# keyboard.net
KiCad netlist of a schematic drawn in EAGLE
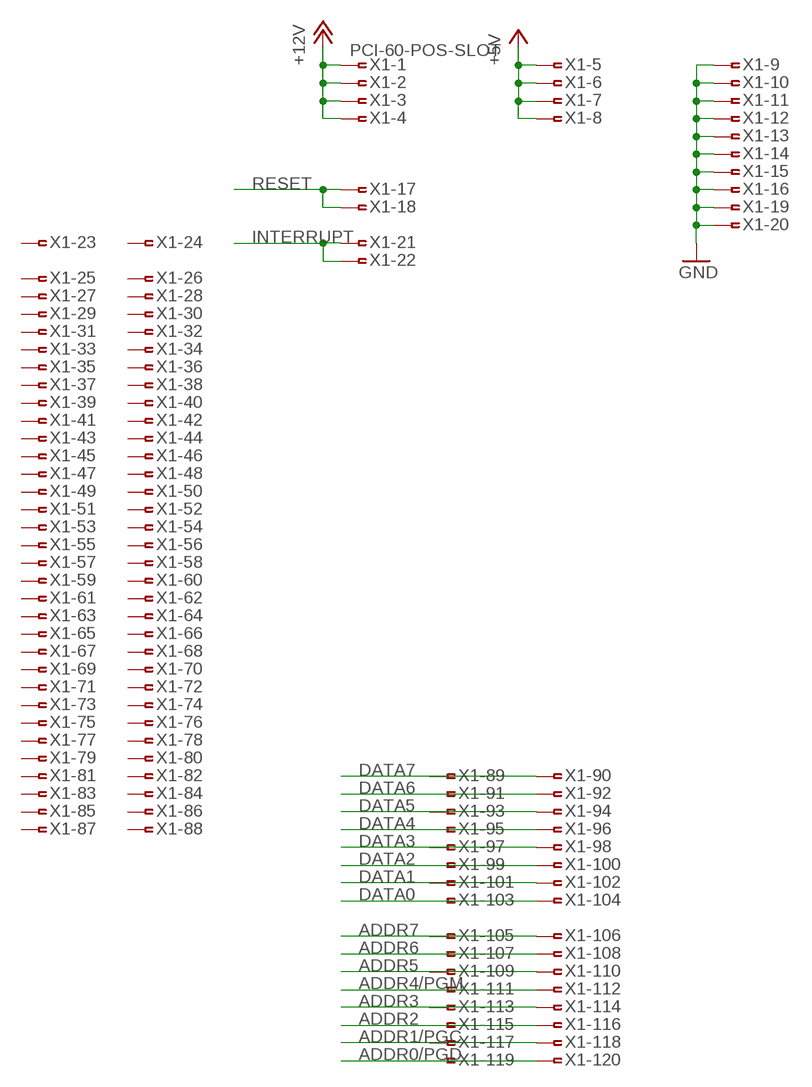
[diagram p0: schematic, sheet 1]
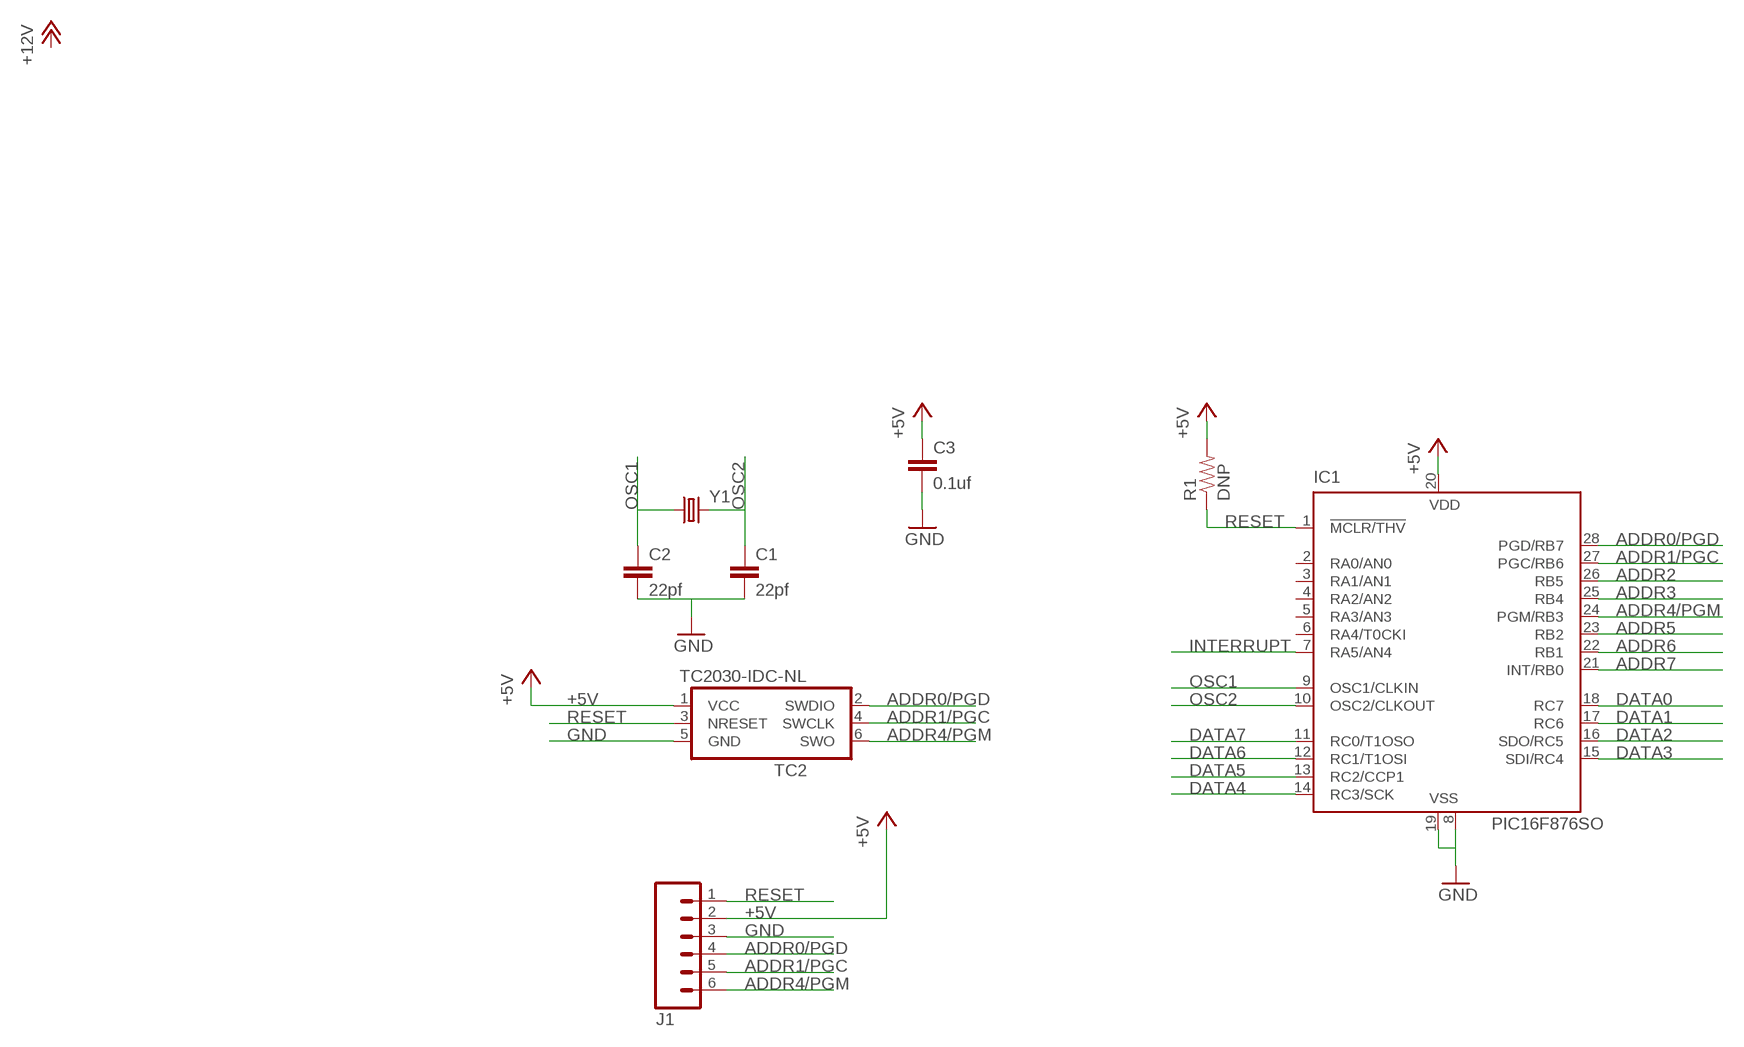
[diagram p1: schematic, sheet 2]

(export (version "E")
  (design (tool "Eeschema 10.0.6"))
  (components
    (comp (ref "C1")
      (value "22pf")
      (footprint "eagle-import:1206")
      (libsource (lib "eagle-import") (part "CAP1206"))
    )
    (comp (ref "C2")
      (value "22pf")
      (footprint "eagle-import:1206")
      (libsource (lib "eagle-import") (part "CAP1206"))
    )
    (comp (ref "C3")
      (value "0.1uf")
      (footprint "eagle-import:1206")
      (libsource (lib "eagle-import") (part "CAP1206"))
    )
    (comp (ref "IC1")
      (value "PIC16F876SO")
      (footprint "eagle-import:SO28W")
      (fields (field (name "MF") "MICROCHIP") (field (name "MPN") "PIC16F876-20/SO"))
      (libsource (lib "eagle-import") (part "PIC16876SOF"))
    )
    (comp (ref "J1")
      (value "M06POLAR_LOCK")
      (footprint "eagle-import:MOLEX-1X6_LOCK")
      (libsource (lib "eagle-import") (part "M06POLAR_LOCK"))
    )
    (comp (ref "R1")
      (value "DNP")
      (footprint "eagle-import:1206")
      (libsource (lib "eagle-import") (part "RESISTOR1206"))
    )
    (comp (ref "TC2")
      (value "TC2030-IDC-NL")
      (footprint "eagle-import:TC2030-IDC-NL")
      (libsource (lib "eagle-import") (part "TC2030-IDC-NL"))
    )
    (comp (ref "Y1")
      (value "CRYSTALSMD")
      (footprint "eagle-import:HC49UP")
      (libsource (lib "eagle-import") (part "CRYSTALSMD"))
    )
    (comp (ref "X1")
      (value "PCI-60-POS-SLOT")
      (footprint "eagle-import:PCI-SLOT-60")
      (libsource (lib "eagle-import") (part "PCI-60-POS-SLOT"))
    )
  )
  (nets
    (net (code "1") (name "+5V") (class "Default")
      (node (ref "C3") (pin "1") (pinfunction "1_1") (pintype "passive"))
      (node (ref "IC1") (pin "20") (pinfunction "VDD_20") (pintype "power_in"))
      (node (ref "J1") (pin "2") (pinfunction "2_2") (pintype "passive"))
      (node (ref "R1") (pin "2") (pinfunction "2_2") (pintype "passive"))
      (node (ref "TC2") (pin "1") (pinfunction "VCC_1") (pintype "passive"))
      (node (ref "X1") (pin "5") (pinfunction "1_5") (pintype "passive"))
      (node (ref "X1") (pin "6") (pinfunction "1_6") (pintype "passive"))
      (node (ref "X1") (pin "7") (pinfunction "1_7") (pintype "passive"))
      (node (ref "X1") (pin "8") (pinfunction "1_8") (pintype "passive"))
    )
    (net (code "2") (name "+12V") (class "Default")
      (node (ref "X1") (pin "1") (pinfunction "1_1") (pintype "passive"))
      (node (ref "X1") (pin "2") (pinfunction "1_2") (pintype "passive"))
      (node (ref "X1") (pin "3") (pinfunction "1_3") (pintype "passive"))
      (node (ref "X1") (pin "4") (pinfunction "1_4") (pintype "passive"))
    )
    (net (code "3") (name "ADDR0{slash}PGD") (class "Default")
      (node (ref "IC1") (pin "28") (pinfunction "PGD/RB7_28") (pintype "bidirectional"))
      (node (ref "J1") (pin "4") (pinfunction "4_4") (pintype "passive"))
      (node (ref "TC2") (pin "2") (pinfunction "SWDIO_2") (pintype "passive"))
      (node (ref "X1") (pin "119") (pinfunction "1_119") (pintype "passive"))
      (node (ref "X1") (pin "120") (pinfunction "1_120") (pintype "passive"))
    )
    (net (code "4") (name "ADDR1{slash}PGC") (class "Default")
      (node (ref "IC1") (pin "27") (pinfunction "PGC/RB6_27") (pintype "bidirectional"))
      (node (ref "J1") (pin "5") (pinfunction "5_5") (pintype "passive"))
      (node (ref "TC2") (pin "4") (pinfunction "SWCLK_4") (pintype "passive"))
      (node (ref "X1") (pin "117") (pinfunction "1_117") (pintype "passive"))
      (node (ref "X1") (pin "118") (pinfunction "1_118") (pintype "passive"))
    )
    (net (code "5") (name "ADDR2") (class "Default")
      (node (ref "IC1") (pin "26") (pinfunction "RB5_26") (pintype "bidirectional"))
      (node (ref "X1") (pin "115") (pinfunction "1_115") (pintype "passive"))
      (node (ref "X1") (pin "116") (pinfunction "1_116") (pintype "passive"))
    )
    (net (code "6") (name "ADDR3") (class "Default")
      (node (ref "IC1") (pin "25") (pinfunction "RB4_25") (pintype "bidirectional"))
      (node (ref "X1") (pin "113") (pinfunction "1_113") (pintype "passive"))
      (node (ref "X1") (pin "114") (pinfunction "1_114") (pintype "passive"))
    )
    (net (code "7") (name "ADDR4{slash}PGM") (class "Default")
      (node (ref "IC1") (pin "24") (pinfunction "PGM/RB3_24") (pintype "bidirectional"))
      (node (ref "J1") (pin "6") (pinfunction "6_6") (pintype "passive"))
      (node (ref "TC2") (pin "6") (pinfunction "SWO_6") (pintype "passive"))
      (node (ref "X1") (pin "111") (pinfunction "1_111") (pintype "passive"))
      (node (ref "X1") (pin "112") (pinfunction "1_112") (pintype "passive"))
    )
    (net (code "8") (name "ADDR5") (class "Default")
      (node (ref "IC1") (pin "23") (pinfunction "RB2_23") (pintype "bidirectional"))
      (node (ref "X1") (pin "109") (pinfunction "1_109") (pintype "passive"))
      (node (ref "X1") (pin "110") (pinfunction "1_110") (pintype "passive"))
    )
    (net (code "9") (name "ADDR6") (class "Default")
      (node (ref "IC1") (pin "22") (pinfunction "RB1_22") (pintype "bidirectional"))
      (node (ref "X1") (pin "107") (pinfunction "1_107") (pintype "passive"))
      (node (ref "X1") (pin "108") (pinfunction "1_108") (pintype "passive"))
    )
    (net (code "10") (name "ADDR7") (class "Default")
      (node (ref "IC1") (pin "21") (pinfunction "INT/RB0_21") (pintype "bidirectional"))
      (node (ref "X1") (pin "105") (pinfunction "1_105") (pintype "passive"))
      (node (ref "X1") (pin "106") (pinfunction "1_106") (pintype "passive"))
    )
    (net (code "11") (name "DATA0") (class "Default")
      (node (ref "IC1") (pin "18") (pinfunction "RC7_18") (pintype "bidirectional"))
      (node (ref "X1") (pin "103") (pinfunction "1_103") (pintype "passive"))
      (node (ref "X1") (pin "104") (pinfunction "1_104") (pintype "passive"))
    )
    (net (code "12") (name "DATA1") (class "Default")
      (node (ref "IC1") (pin "17") (pinfunction "RC6_17") (pintype "bidirectional"))
      (node (ref "X1") (pin "101") (pinfunction "1_101") (pintype "passive"))
      (node (ref "X1") (pin "102") (pinfunction "1_102") (pintype "passive"))
    )
    (net (code "13") (name "DATA2") (class "Default")
      (node (ref "IC1") (pin "16") (pinfunction "SDO/RC5_16") (pintype "bidirectional"))
      (node (ref "X1") (pin "100") (pinfunction "1_100") (pintype "passive"))
      (node (ref "X1") (pin "99") (pinfunction "1_99") (pintype "passive"))
    )
    (net (code "14") (name "DATA3") (class "Default")
      (node (ref "IC1") (pin "15") (pinfunction "SDI/RC4_15") (pintype "bidirectional"))
      (node (ref "X1") (pin "97") (pinfunction "1_97") (pintype "passive"))
      (node (ref "X1") (pin "98") (pinfunction "1_98") (pintype "passive"))
    )
    (net (code "15") (name "DATA4") (class "Default")
      (node (ref "IC1") (pin "14") (pinfunction "RC3/SCK_14") (pintype "bidirectional"))
      (node (ref "X1") (pin "95") (pinfunction "1_95") (pintype "passive"))
      (node (ref "X1") (pin "96") (pinfunction "1_96") (pintype "passive"))
    )
    (net (code "16") (name "DATA5") (class "Default")
      (node (ref "IC1") (pin "13") (pinfunction "RC2/CCP1_13") (pintype "bidirectional"))
      (node (ref "X1") (pin "93") (pinfunction "1_93") (pintype "passive"))
      (node (ref "X1") (pin "94") (pinfunction "1_94") (pintype "passive"))
    )
    (net (code "17") (name "DATA6") (class "Default")
      (node (ref "IC1") (pin "12") (pinfunction "RC1/T1OSI_12") (pintype "bidirectional"))
      (node (ref "X1") (pin "91") (pinfunction "1_91") (pintype "passive"))
      (node (ref "X1") (pin "92") (pinfunction "1_92") (pintype "passive"))
    )
    (net (code "18") (name "DATA7") (class "Default")
      (node (ref "IC1") (pin "11") (pinfunction "RC0/T1OSO_11") (pintype "bidirectional"))
      (node (ref "X1") (pin "89") (pinfunction "1_89") (pintype "passive"))
      (node (ref "X1") (pin "90") (pinfunction "1_90") (pintype "passive"))
    )
    (net (code "19") (name "GND") (class "Default")
      (node (ref "C1") (pin "2") (pinfunction "2_2") (pintype "passive"))
      (node (ref "C2") (pin "2") (pinfunction "2_2") (pintype "passive"))
      (node (ref "C3") (pin "2") (pinfunction "2_2") (pintype "passive"))
      (node (ref "IC1") (pin "19") (pinfunction "VSS_19") (pintype "power_in"))
      (node (ref "IC1") (pin "8") (pinfunction "VSS_8") (pintype "power_in"))
      (node (ref "J1") (pin "3") (pinfunction "3_3") (pintype "passive"))
      (node (ref "TC2") (pin "5") (pinfunction "GND_5") (pintype "passive"))
      (node (ref "X1") (pin "10") (pinfunction "1_10") (pintype "passive"))
      (node (ref "X1") (pin "11") (pinfunction "1_11") (pintype "passive"))
      (node (ref "X1") (pin "12") (pinfunction "1_12") (pintype "passive"))
      (node (ref "X1") (pin "13") (pinfunction "1_13") (pintype "passive"))
      (node (ref "X1") (pin "14") (pinfunction "1_14") (pintype "passive"))
      (node (ref "X1") (pin "15") (pinfunction "1_15") (pintype "passive"))
      (node (ref "X1") (pin "16") (pinfunction "1_16") (pintype "passive"))
      (node (ref "X1") (pin "19") (pinfunction "1_19") (pintype "passive"))
      (node (ref "X1") (pin "20") (pinfunction "1_20") (pintype "passive"))
      (node (ref "X1") (pin "9") (pinfunction "1_9") (pintype "passive"))
    )
    (net (code "20") (name "INTERRUPT") (class "Default")
      (node (ref "IC1") (pin "7") (pinfunction "RA5/AN4_7") (pintype "bidirectional"))
      (node (ref "X1") (pin "21") (pinfunction "1_21") (pintype "passive"))
      (node (ref "X1") (pin "22") (pinfunction "1_22") (pintype "passive"))
    )
    (net (code "21") (name "OSC1") (class "Default")
      (node (ref "C2") (pin "1") (pinfunction "1_1") (pintype "passive"))
      (node (ref "IC1") (pin "9") (pinfunction "OSC1/CLKIN_9") (pintype "input"))
      (node (ref "Y1") (pin "1") (pinfunction "1_1") (pintype "passive"))
    )
    (net (code "22") (name "OSC2") (class "Default")
      (node (ref "C1") (pin "1") (pinfunction "1_1") (pintype "passive"))
      (node (ref "IC1") (pin "10") (pinfunction "OSC2/CLKOUT_10") (pintype "output"))
      (node (ref "Y1") (pin "2") (pinfunction "2_2") (pintype "passive"))
    )
    (net (code "23") (name "RESET") (class "Default")
      (node (ref "IC1") (pin "1") (pinfunction "~{MCLR/THV}_1") (pintype "input"))
      (node (ref "J1") (pin "1") (pinfunction "1_1") (pintype "passive"))
      (node (ref "R1") (pin "1") (pinfunction "1_1") (pintype "passive"))
      (node (ref "TC2") (pin "3") (pinfunction "NRESET_3") (pintype "passive"))
      (node (ref "X1") (pin "17") (pinfunction "1_17") (pintype "passive"))
      (node (ref "X1") (pin "18") (pinfunction "1_18") (pintype "passive"))
    )
    (net (code "24") (name "unconnected-(IC1-RA0{slash}AN0-Pad2)") (class "Default")
      (node (ref "IC1") (pin "2") (pinfunction "RA0/AN0_2") (pintype "bidirectional"))
    )
    (net (code "25") (name "unconnected-(IC1-RA1{slash}AN1-Pad3)") (class "Default")
      (node (ref "IC1") (pin "3") (pinfunction "RA1/AN1_3") (pintype "bidirectional"))
    )
    (net (code "26") (name "unconnected-(IC1-RA2{slash}AN2-Pad4)") (class "Default")
      (node (ref "IC1") (pin "4") (pinfunction "RA2/AN2_4") (pintype "bidirectional"))
    )
    (net (code "27") (name "unconnected-(IC1-RA3{slash}AN3-Pad5)") (class "Default")
      (node (ref "IC1") (pin "5") (pinfunction "RA3/AN3_5") (pintype "bidirectional"))
    )
    (net (code "28") (name "unconnected-(IC1-RA4{slash}T0CKI-Pad6)") (class "Default")
      (node (ref "IC1") (pin "6") (pinfunction "RA4/T0CKI_6") (pintype "bidirectional"))
    )
    (net (code "29") (name "unconnected-(X1AK-1-Pad23)") (class "Default")
      (node (ref "X1") (pin "23") (pinfunction "1_23") (pintype "passive"))
    )
    (net (code "30") (name "unconnected-(X1AL-1-Pad24)") (class "Default")
      (node (ref "X1") (pin "24") (pinfunction "1_24") (pintype "passive"))
    )
    (net (code "31") (name "unconnected-(X1AM-1-Pad25)") (class "Default")
      (node (ref "X1") (pin "25") (pinfunction "1_25") (pintype "passive"))
    )
    (net (code "32") (name "unconnected-(X1AN-1-Pad26)") (class "Default")
      (node (ref "X1") (pin "26") (pinfunction "1_26") (pintype "passive"))
    )
    (net (code "33") (name "unconnected-(X1AO-1-Pad27)") (class "Default")
      (node (ref "X1") (pin "27") (pinfunction "1_27") (pintype "passive"))
    )
    (net (code "34") (name "unconnected-(X1AP-1-Pad28)") (class "Default")
      (node (ref "X1") (pin "28") (pinfunction "1_28") (pintype "passive"))
    )
    (net (code "35") (name "unconnected-(X1AQ-1-Pad29)") (class "Default")
      (node (ref "X1") (pin "29") (pinfunction "1_29") (pintype "passive"))
    )
    (net (code "36") (name "unconnected-(X1AS-1-Pad30)") (class "Default")
      (node (ref "X1") (pin "30") (pinfunction "1_30") (pintype "passive"))
    )
    (net (code "37") (name "unconnected-(X1AT-1-Pad31)") (class "Default")
      (node (ref "X1") (pin "31") (pinfunction "1_31") (pintype "passive"))
    )
    (net (code "38") (name "unconnected-(X1AU-1-Pad32)") (class "Default")
      (node (ref "X1") (pin "32") (pinfunction "1_32") (pintype "passive"))
    )
    (net (code "39") (name "unconnected-(X1AV-1-Pad33)") (class "Default")
      (node (ref "X1") (pin "33") (pinfunction "1_33") (pintype "passive"))
    )
    (net (code "40") (name "unconnected-(X1AW-1-Pad34)") (class "Default")
      (node (ref "X1") (pin "34") (pinfunction "1_34") (pintype "passive"))
    )
    (net (code "41") (name "unconnected-(X1AX-1-Pad35)") (class "Default")
      (node (ref "X1") (pin "35") (pinfunction "1_35") (pintype "passive"))
    )
    (net (code "42") (name "unconnected-(X1AY-1-Pad36)") (class "Default")
      (node (ref "X1") (pin "36") (pinfunction "1_36") (pintype "passive"))
    )
    (net (code "43") (name "unconnected-(X1AZ-1-Pad37)") (class "Default")
      (node (ref "X1") (pin "37") (pinfunction "1_37") (pintype "passive"))
    )
    (net (code "44") (name "unconnected-(X1BA-1-Pad38)") (class "Default")
      (node (ref "X1") (pin "38") (pinfunction "1_38") (pintype "passive"))
    )
    (net (code "45") (name "unconnected-(X1BB-1-Pad39)") (class "Default")
      (node (ref "X1") (pin "39") (pinfunction "1_39") (pintype "passive"))
    )
    (net (code "46") (name "unconnected-(X1BD-1-Pad40)") (class "Default")
      (node (ref "X1") (pin "40") (pinfunction "1_40") (pintype "passive"))
    )
    (net (code "47") (name "unconnected-(X1BE-1-Pad41)") (class "Default")
      (node (ref "X1") (pin "41") (pinfunction "1_41") (pintype "passive"))
    )
    (net (code "48") (name "unconnected-(X1BF-1-Pad42)") (class "Default")
      (node (ref "X1") (pin "42") (pinfunction "1_42") (pintype "passive"))
    )
    (net (code "49") (name "unconnected-(X1BG-1-Pad43)") (class "Default")
      (node (ref "X1") (pin "43") (pinfunction "1_43") (pintype "passive"))
    )
    (net (code "50") (name "unconnected-(X1BH-1-Pad44)") (class "Default")
      (node (ref "X1") (pin "44") (pinfunction "1_44") (pintype "passive"))
    )
    (net (code "51") (name "unconnected-(X1BI-1-Pad45)") (class "Default")
      (node (ref "X1") (pin "45") (pinfunction "1_45") (pintype "passive"))
    )
    (net (code "52") (name "unconnected-(X1BJ-1-Pad46)") (class "Default")
      (node (ref "X1") (pin "46") (pinfunction "1_46") (pintype "passive"))
    )
    (net (code "53") (name "unconnected-(X1BK-1-Pad47)") (class "Default")
      (node (ref "X1") (pin "47") (pinfunction "1_47") (pintype "passive"))
    )
    (net (code "54") (name "unconnected-(X1BL-1-Pad48)") (class "Default")
      (node (ref "X1") (pin "48") (pinfunction "1_48") (pintype "passive"))
    )
    (net (code "55") (name "unconnected-(X1BM-1-Pad49)") (class "Default")
      (node (ref "X1") (pin "49") (pinfunction "1_49") (pintype "passive"))
    )
    (net (code "56") (name "unconnected-(X1BO-1-Pad50)") (class "Default")
      (node (ref "X1") (pin "50") (pinfunction "1_50") (pintype "passive"))
    )
    (net (code "57") (name "unconnected-(X1BP-1-Pad51)") (class "Default")
      (node (ref "X1") (pin "51") (pinfunction "1_51") (pintype "passive"))
    )
    (net (code "58") (name "unconnected-(X1BQ-1-Pad52)") (class "Default")
      (node (ref "X1") (pin "52") (pinfunction "1_52") (pintype "passive"))
    )
    (net (code "59") (name "unconnected-(X1BR-1-Pad53)") (class "Default")
      (node (ref "X1") (pin "53") (pinfunction "1_53") (pintype "passive"))
    )
    (net (code "60") (name "unconnected-(X1BS-1-Pad54)") (class "Default")
      (node (ref "X1") (pin "54") (pinfunction "1_54") (pintype "passive"))
    )
    (net (code "61") (name "unconnected-(X1BT-1-Pad55)") (class "Default")
      (node (ref "X1") (pin "55") (pinfunction "1_55") (pintype "passive"))
    )
    (net (code "62") (name "unconnected-(X1BU-1-Pad56)") (class "Default")
      (node (ref "X1") (pin "56") (pinfunction "1_56") (pintype "passive"))
    )
    (net (code "63") (name "unconnected-(X1BV-1-Pad57)") (class "Default")
      (node (ref "X1") (pin "57") (pinfunction "1_57") (pintype "passive"))
    )
    (net (code "64") (name "unconnected-(X1BW-1-Pad58)") (class "Default")
      (node (ref "X1") (pin "58") (pinfunction "1_58") (pintype "passive"))
    )
    (net (code "65") (name "unconnected-(X1BX-1-Pad59)") (class "Default")
      (node (ref "X1") (pin "59") (pinfunction "1_59") (pintype "passive"))
    )
    (net (code "66") (name "unconnected-(X1BZ-1-Pad60)") (class "Default")
      (node (ref "X1") (pin "60") (pinfunction "1_60") (pintype "passive"))
    )
    (net (code "67") (name "unconnected-(X1CA-1-Pad61)") (class "Default")
      (node (ref "X1") (pin "61") (pinfunction "1_61") (pintype "passive"))
    )
    (net (code "68") (name "unconnected-(X1CB-1-Pad62)") (class "Default")
      (node (ref "X1") (pin "62") (pinfunction "1_62") (pintype "passive"))
    )
    (net (code "69") (name "unconnected-(X1CC-1-Pad63)") (class "Default")
      (node (ref "X1") (pin "63") (pinfunction "1_63") (pintype "passive"))
    )
    (net (code "70") (name "unconnected-(X1CD-1-Pad64)") (class "Default")
      (node (ref "X1") (pin "64") (pinfunction "1_64") (pintype "passive"))
    )
    (net (code "71") (name "unconnected-(X1CE-1-Pad65)") (class "Default")
      (node (ref "X1") (pin "65") (pinfunction "1_65") (pintype "passive"))
    )
    (net (code "72") (name "unconnected-(X1CF-1-Pad66)") (class "Default")
      (node (ref "X1") (pin "66") (pinfunction "1_66") (pintype "passive"))
    )
    (net (code "73") (name "unconnected-(X1CG-1-Pad67)") (class "Default")
      (node (ref "X1") (pin "67") (pinfunction "1_67") (pintype "passive"))
    )
    (net (code "74") (name "unconnected-(X1CH-1-Pad68)") (class "Default")
      (node (ref "X1") (pin "68") (pinfunction "1_68") (pintype "passive"))
    )
    (net (code "75") (name "unconnected-(X1CI-1-Pad69)") (class "Default")
      (node (ref "X1") (pin "69") (pinfunction "1_69") (pintype "passive"))
    )
    (net (code "76") (name "unconnected-(X1CK-1-Pad70)") (class "Default")
      (node (ref "X1") (pin "70") (pinfunction "1_70") (pintype "passive"))
    )
    (net (code "77") (name "unconnected-(X1CL-1-Pad71)") (class "Default")
      (node (ref "X1") (pin "71") (pinfunction "1_71") (pintype "passive"))
    )
    (net (code "78") (name "unconnected-(X1CM-1-Pad72)") (class "Default")
      (node (ref "X1") (pin "72") (pinfunction "1_72") (pintype "passive"))
    )
    (net (code "79") (name "unconnected-(X1CN-1-Pad73)") (class "Default")
      (node (ref "X1") (pin "73") (pinfunction "1_73") (pintype "passive"))
    )
    (net (code "80") (name "unconnected-(X1CO-1-Pad74)") (class "Default")
      (node (ref "X1") (pin "74") (pinfunction "1_74") (pintype "passive"))
    )
    (net (code "81") (name "unconnected-(X1CP-1-Pad75)") (class "Default")
      (node (ref "X1") (pin "75") (pinfunction "1_75") (pintype "passive"))
    )
    (net (code "82") (name "unconnected-(X1CQ-1-Pad76)") (class "Default")
      (node (ref "X1") (pin "76") (pinfunction "1_76") (pintype "passive"))
    )
    (net (code "83") (name "unconnected-(X1CR-1-Pad77)") (class "Default")
      (node (ref "X1") (pin "77") (pinfunction "1_77") (pintype "passive"))
    )
    (net (code "84") (name "unconnected-(X1CS-1-Pad78)") (class "Default")
      (node (ref "X1") (pin "78") (pinfunction "1_78") (pintype "passive"))
    )
    (net (code "85") (name "unconnected-(X1CT-1-Pad79)") (class "Default")
      (node (ref "X1") (pin "79") (pinfunction "1_79") (pintype "passive"))
    )
    (net (code "86") (name "unconnected-(X1CV-1-Pad80)") (class "Default")
      (node (ref "X1") (pin "80") (pinfunction "1_80") (pintype "passive"))
    )
    (net (code "87") (name "unconnected-(X1CW-1-Pad81)") (class "Default")
      (node (ref "X1") (pin "81") (pinfunction "1_81") (pintype "passive"))
    )
    (net (code "88") (name "unconnected-(X1CX-1-Pad82)") (class "Default")
      (node (ref "X1") (pin "82") (pinfunction "1_82") (pintype "passive"))
    )
    (net (code "89") (name "unconnected-(X1CY-1-Pad83)") (class "Default")
      (node (ref "X1") (pin "83") (pinfunction "1_83") (pintype "passive"))
    )
    (net (code "90") (name "unconnected-(X1CZ-1-Pad84)") (class "Default")
      (node (ref "X1") (pin "84") (pinfunction "1_84") (pintype "passive"))
    )
    (net (code "91") (name "unconnected-(X1DA-1-Pad85)") (class "Default")
      (node (ref "X1") (pin "85") (pinfunction "1_85") (pintype "passive"))
    )
    (net (code "92") (name "unconnected-(X1DB-1-Pad86)") (class "Default")
      (node (ref "X1") (pin "86") (pinfunction "1_86") (pintype "passive"))
    )
    (net (code "93") (name "unconnected-(X1DC-1-Pad87)") (class "Default")
      (node (ref "X1") (pin "87") (pinfunction "1_87") (pintype "passive"))
    )
    (net (code "94") (name "unconnected-(X1DD-1-Pad88)") (class "Default")
      (node (ref "X1") (pin "88") (pinfunction "1_88") (pintype "passive"))
    )
  )
)
